# Controll.net
KiCad netlist of a schematic drawn in Altium Designer
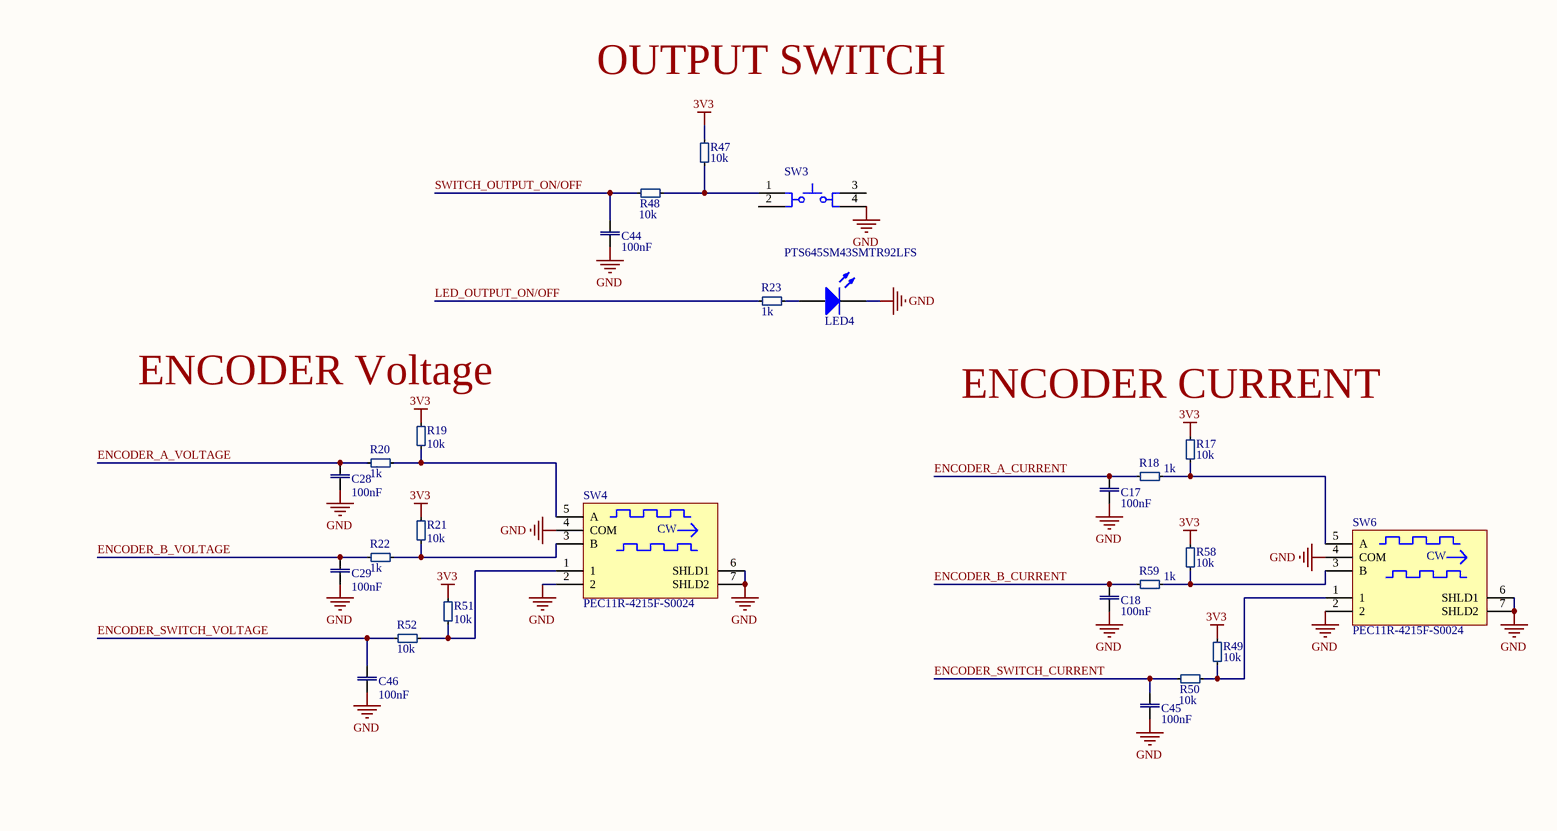
[diagram p0: Controll.SchDoc, top left]
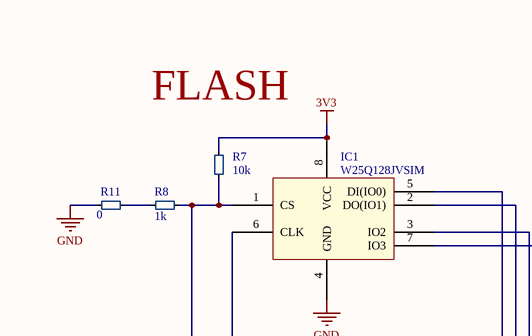
[diagram p1: Controll.SchDoc, top right]
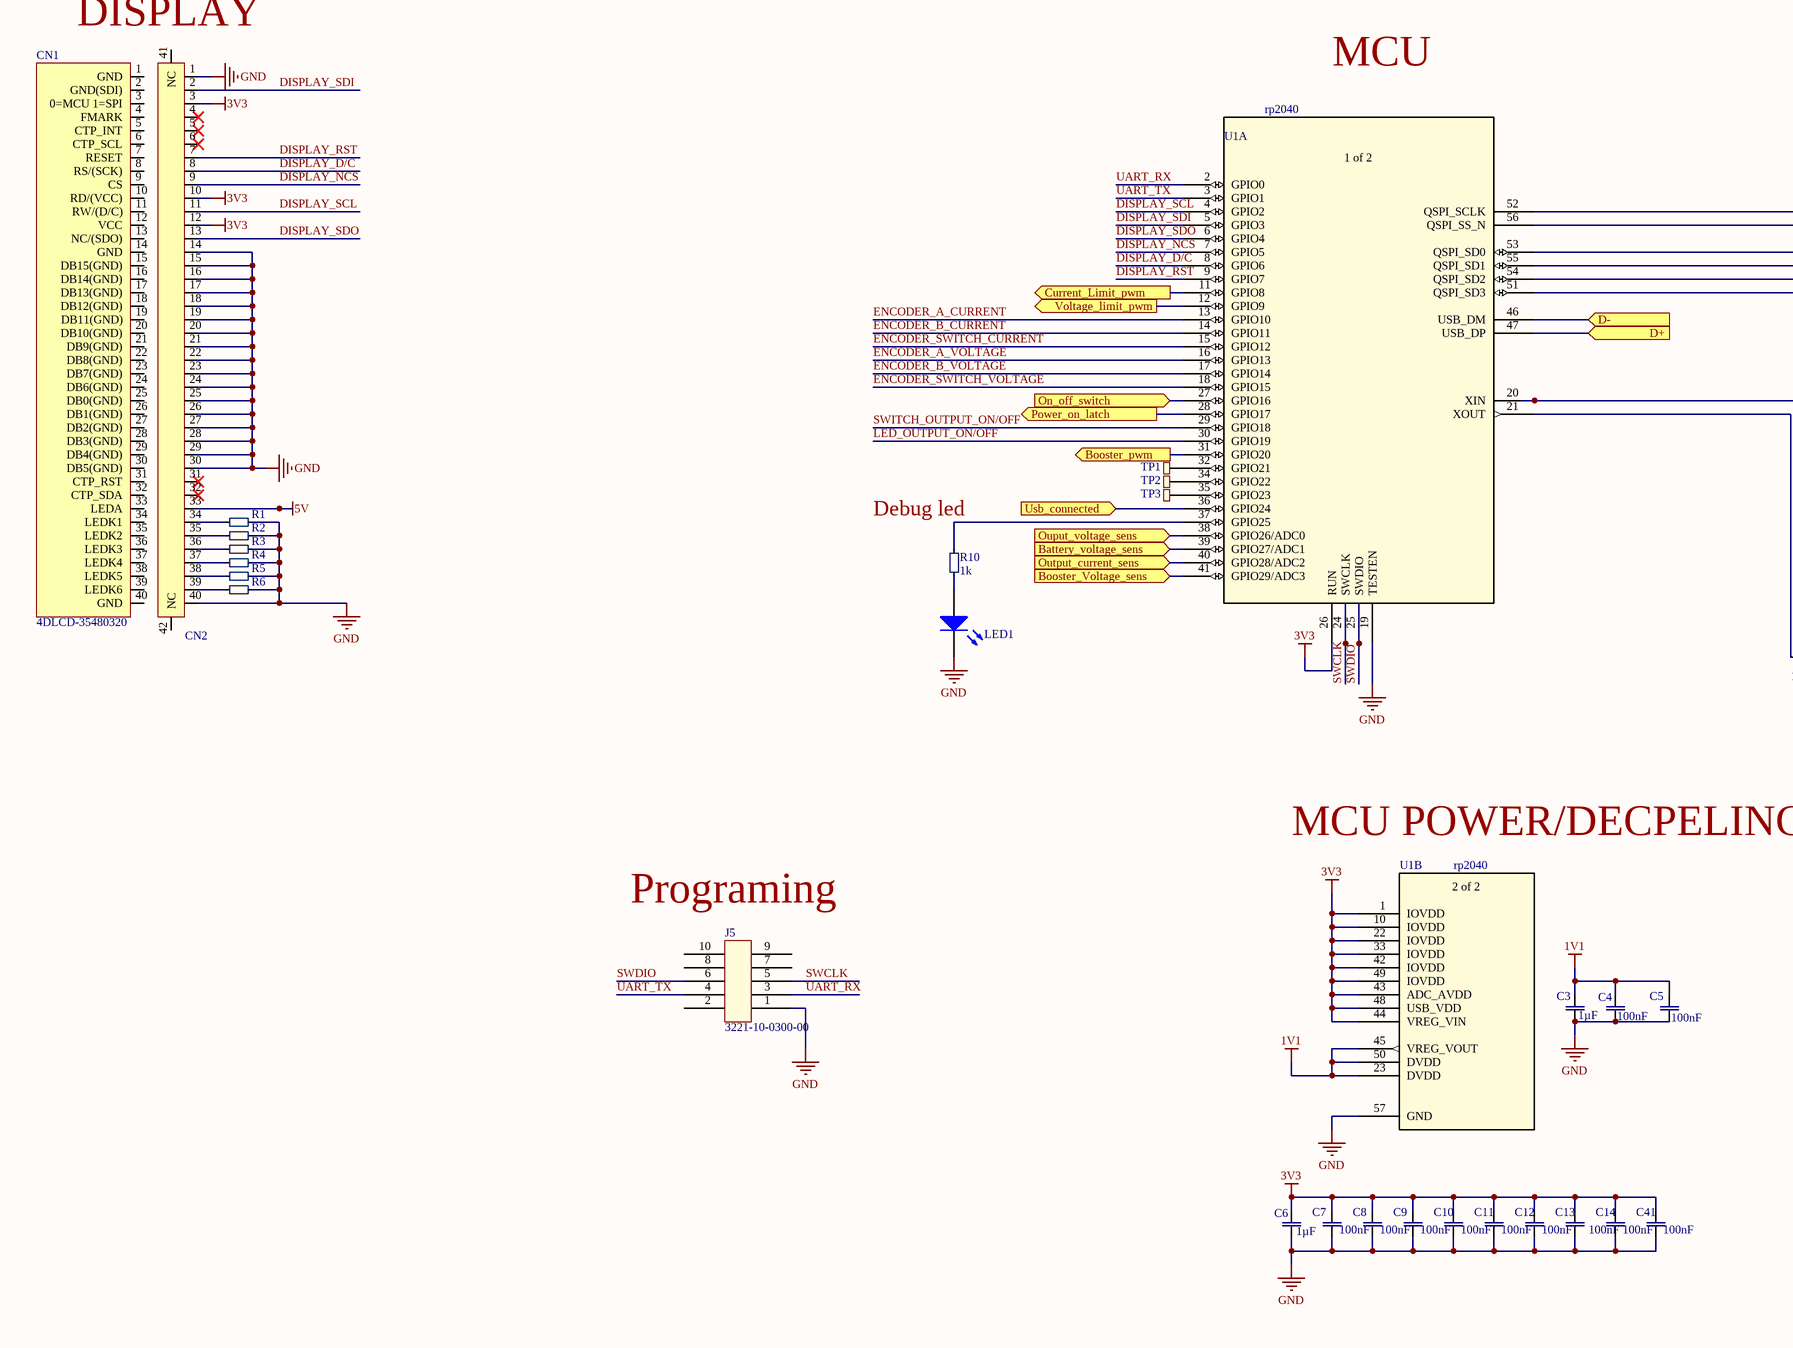
[diagram p2: Controll.SchDoc, bottom left]
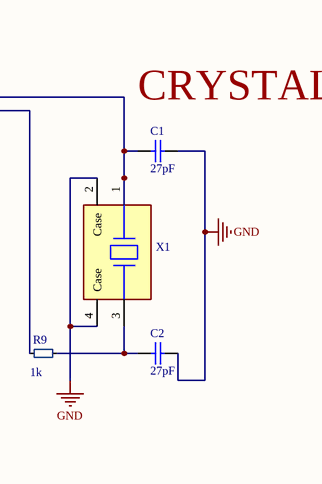
[diagram p3: Controll.SchDoc, bottom right]

(export (version "E")
  (design (tool "Eeschema 10.0.6"))
  (components
    (comp (ref "C1")
      (value "04025A270KAT2A")
      (footprint "cap0402")
      (description "0402 27 pF 50 V ±10 % Tolerance C0G/NP0 SMT Multilayer Ceramic Capacitor")
      (fields
        (field (name "CAPACITANCE") "27pF")
        (field (name "TOLERANCE") "10%")
        (field (name "LCSC PART#") "C2168514")
      )
      (libsource (lib "concord server") (part "CAP"))
    )
    (comp (ref "C2")
      (value "04025A270KAT2A")
      (footprint "cap0402")
      (description "0402 27 pF 50 V ±10 % Tolerance C0G/NP0 SMT Multilayer Ceramic Capacitor")
      (fields
        (field (name "CAPACITANCE") "27pF")
        (field (name "TOLERANCE") "10%")
        (field (name "LCSC PART#") "C2168514")
      )
      (libsource (lib "concord server") (part "CAP"))
    )
    (comp (ref "C3")
      (value "CL21B105KBFNNNG")
      (footprint "CAP0805")
      (description "SAMSUNG ELECTRO-MECHANICS - CL21B105KBFNNNG - MLCC CAPACITORS")
      (fields
        (field (name "VOLTAGE") "50V")
        (field (name "CAPACITANCE") "1µF")
        (field (name "TOLERANCE") "10%")
      )
      (libsource (lib "concord server") (part "Capasitor_keramic_generic"))
    )
    (comp (ref "C4")
      (value "GRM155R71H104ME14D")
      (footprint "cap0402")
      (description "0402 0.1 uF 50 V ±20% Tolerance X7R SMT Monolithic Ceramic Chip Capacitor")
      (fields
        (field (name "CAPACITANCE") "100nF")
        (field (name "TOLERANCE") "20%")
        (field (name "LCSC PART#") "C182412")
      )
      (libsource (lib "concord server") (part "Capasitor_keramic_generic"))
    )
    (comp (ref "C5")
      (value "GRM155R71H104ME14D")
      (footprint "cap0402")
      (description "0402 0.1 uF 50 V ±20% Tolerance X7R SMT Monolithic Ceramic Chip Capacitor")
      (fields
        (field (name "CAPACITANCE") "100nF")
        (field (name "TOLERANCE") "20%")
        (field (name "LCSC PART#") "C182412")
      )
      (libsource (lib "concord server") (part "Capasitor_keramic_generic"))
    )
    (comp (ref "C6")
      (value "CL21B105KBFNNNG")
      (footprint "CAP0805")
      (description "SAMSUNG ELECTRO-MECHANICS - CL21B105KBFNNNG - MLCC CAPACITORS")
      (fields
        (field (name "VOLTAGE") "50V")
        (field (name "CAPACITANCE") "1µF")
        (field (name "TOLERANCE") "10%")
      )
      (libsource (lib "concord server") (part "Capasitor_keramic_generic"))
    )
    (comp (ref "C7")
      (value "GRM155R71H104ME14D")
      (footprint "cap0402")
      (description "0402 0.1 uF 50 V ±20% Tolerance X7R SMT Monolithic Ceramic Chip Capacitor")
      (fields
        (field (name "CAPACITANCE") "100nF")
        (field (name "TOLERANCE") "20%")
        (field (name "LCSC PART#") "C182412")
      )
      (libsource (lib "concord server") (part "Capasitor_keramic_generic"))
    )
    (comp (ref "C8")
      (value "GRM155R71H104ME14D")
      (footprint "cap0402")
      (description "0402 0.1 uF 50 V ±20% Tolerance X7R SMT Monolithic Ceramic Chip Capacitor")
      (fields
        (field (name "CAPACITANCE") "100nF")
        (field (name "TOLERANCE") "20%")
        (field (name "LCSC PART#") "C182412")
      )
      (libsource (lib "concord server") (part "Capasitor_keramic_generic"))
    )
    (comp (ref "C9")
      (value "GRM155R71H104ME14D")
      (footprint "cap0402")
      (description "0402 0.1 uF 50 V ±20% Tolerance X7R SMT Monolithic Ceramic Chip Capacitor")
      (fields
        (field (name "CAPACITANCE") "100nF")
        (field (name "TOLERANCE") "20%")
        (field (name "LCSC PART#") "C182412")
      )
      (libsource (lib "concord server") (part "Capasitor_keramic_generic"))
    )
    (comp (ref "C10")
      (value "GRM155R71H104ME14D")
      (footprint "cap0402")
      (description "0402 0.1 uF 50 V ±20% Tolerance X7R SMT Monolithic Ceramic Chip Capacitor")
      (fields
        (field (name "CAPACITANCE") "100nF")
        (field (name "TOLERANCE") "20%")
        (field (name "LCSC PART#") "C182412")
      )
      (libsource (lib "concord server") (part "Capasitor_keramic_generic"))
    )
    (comp (ref "C11")
      (value "GRM155R71H104ME14D")
      (footprint "cap0402")
      (description "0402 0.1 uF 50 V ±20% Tolerance X7R SMT Monolithic Ceramic Chip Capacitor")
      (fields
        (field (name "CAPACITANCE") "100nF")
        (field (name "TOLERANCE") "20%")
        (field (name "LCSC PART#") "C182412")
      )
      (libsource (lib "concord server") (part "Capasitor_keramic_generic"))
    )
    (comp (ref "C12")
      (value "GRM155R71H104ME14D")
      (footprint "cap0402")
      (description "0402 0.1 uF 50 V ±20% Tolerance X7R SMT Monolithic Ceramic Chip Capacitor")
      (fields
        (field (name "CAPACITANCE") "100nF")
        (field (name "TOLERANCE") "20%")
        (field (name "LCSC PART#") "C182412")
      )
      (libsource (lib "concord server") (part "Capasitor_keramic_generic"))
    )
    (comp (ref "C13")
      (value "GRM155R71H104ME14D")
      (footprint "cap0402")
      (description "0402 0.1 uF 50 V ±20% Tolerance X7R SMT Monolithic Ceramic Chip Capacitor")
      (fields
        (field (name "CAPACITANCE") "100nF")
        (field (name "TOLERANCE") "20%")
        (field (name "LCSC PART#") "C182412")
      )
      (libsource (lib "concord server") (part "Capasitor_keramic_generic"))
    )
    (comp (ref "C14")
      (value "GRM155R71H104ME14D")
      (footprint "cap0402")
      (description "0402 0.1 uF 50 V ±20% Tolerance X7R SMT Monolithic Ceramic Chip Capacitor")
      (fields
        (field (name "CAPACITANCE") "100nF")
        (field (name "TOLERANCE") "20%")
        (field (name "LCSC PART#") "C182412")
      )
      (libsource (lib "concord server") (part "Capasitor_keramic_generic"))
    )
    (comp (ref "C17")
      (value "GRM155R71H104ME14D")
      (footprint "cap0402")
      (description "0402 0.1 uF 50 V ±20% Tolerance X7R SMT Monolithic Ceramic Chip Capacitor")
      (fields
        (field (name "CAPACITANCE") "100nF")
        (field (name "TOLERANCE") "20%")
        (field (name "LCSC PART#") "C182412")
      )
      (libsource (lib "concord server") (part "Capasitor_keramic_generic"))
    )
    (comp (ref "C18")
      (value "GRM155R71H104ME14D")
      (footprint "cap0402")
      (description "0402 0.1 uF 50 V ±20% Tolerance X7R SMT Monolithic Ceramic Chip Capacitor")
      (fields
        (field (name "CAPACITANCE") "100nF")
        (field (name "TOLERANCE") "20%")
        (field (name "LCSC PART#") "C182412")
      )
      (libsource (lib "concord server") (part "Capasitor_keramic_generic"))
    )
    (comp (ref "C28")
      (value "GRM155R71H104ME14D")
      (footprint "cap0402")
      (description "0402 0.1 uF 50 V ±20% Tolerance X7R SMT Monolithic Ceramic Chip Capacitor")
      (fields
        (field (name "CAPACITANCE") "100nF")
        (field (name "TOLERANCE") "20%")
        (field (name "LCSC PART#") "C182412")
      )
      (libsource (lib "concord server") (part "Capasitor_keramic_generic"))
    )
    (comp (ref "C29")
      (value "GRM155R71H104ME14D")
      (footprint "cap0402")
      (description "0402 0.1 uF 50 V ±20% Tolerance X7R SMT Monolithic Ceramic Chip Capacitor")
      (fields
        (field (name "CAPACITANCE") "100nF")
        (field (name "TOLERANCE") "20%")
        (field (name "LCSC PART#") "C182412")
      )
      (libsource (lib "concord server") (part "Capasitor_keramic_generic"))
    )
    (comp (ref "C41")
      (value "GRM155R71H104ME14D")
      (footprint "cap0402")
      (description "0402 0.1 uF 50 V ±20% Tolerance X7R SMT Monolithic Ceramic Chip Capacitor")
      (fields
        (field (name "CAPACITANCE") "100nF")
        (field (name "TOLERANCE") "20%")
        (field (name "LCSC PART#") "C182412")
      )
      (libsource (lib "concord server") (part "Capasitor_keramic_generic"))
    )
    (comp (ref "C44")
      (value "GRM155R71H104ME14D")
      (footprint "cap0402")
      (description "0402 0.1 uF 50 V ±20% Tolerance X7R SMT Monolithic Ceramic Chip Capacitor")
      (fields
        (field (name "CAPACITANCE") "100nF")
        (field (name "TOLERANCE") "20%")
        (field (name "LCSC PART#") "C182412")
      )
      (libsource (lib "concord server") (part "Capasitor_keramic_generic"))
    )
    (comp (ref "C45")
      (value "GRM155R71H104ME14D")
      (footprint "cap0402")
      (description "0402 0.1 uF 50 V ±20% Tolerance X7R SMT Monolithic Ceramic Chip Capacitor")
      (fields
        (field (name "CAPACITANCE") "100nF")
        (field (name "TOLERANCE") "20%")
        (field (name "LCSC PART#") "C182412")
      )
      (libsource (lib "concord server") (part "Capasitor_keramic_generic"))
    )
    (comp (ref "C46")
      (value "GRM155R71H104ME14D")
      (footprint "cap0402")
      (description "0402 0.1 uF 50 V ±20% Tolerance X7R SMT Monolithic Ceramic Chip Capacitor")
      (fields
        (field (name "CAPACITANCE") "100nF")
        (field (name "TOLERANCE") "20%")
        (field (name "LCSC PART#") "C182412")
      )
      (libsource (lib "concord server") (part "Capasitor_keramic_generic"))
    )
    (comp (ref "CN1") (value "4DLCD-35480320") (libsource (lib "concord server") (part "4DLCD-35480320")))
    (comp (ref "CN2")
      (value "505110-4091")
      (footprint "505110-4091-Footprint-1")
      (libsource (lib "concord server") (part "505110-4091"))
    )
    (comp (ref "IC1")
      (value "W25Q128JVSIM")
      (footprint "SOIC127P780X195-8N")
      (description "NOR Flash Serial (SPI, Dual SPI, Quad SPI) 3V/3.3V 128M-bit 16M x 8 6ns 8-Pin SOIC Tube")
      (fields (field (name "LCSC PART#") "C2613930"))
      (libsource (lib "concord server") (part "W25Q128JVSIM-Symbol-1"))
    )
    (comp (ref "J5")
      (value "3221-10-0300-00")
      (footprint "New footprint 1")
      (description "Conn Shrouded Header HDR 10 POS 1.27mm Solder ST SMD")
      (libsource (lib "concord server") (part "3221-10-0300-00-Symbol-1"))
    )
    (comp (ref "LED1")
      (value "150080BS75000")
      (footprint "0805_A")
      (description "SMD LED blue 3.5 V 0805, 150080BS75000, Würth Elektronik")
      (libsource (lib "concord server") (part "WE-LED_K1A2-2"))
    )
    (comp (ref "LED4")
      (value "150080BS75000")
      (footprint "0805_A")
      (description "SMD LED blue 3.5 V 0805, 150080BS75000, Würth Elektronik")
      (libsource (lib "concord server") (part "WE-LED_K1A2-2"))
    )
    (comp (ref "R1")
      (value "RC0402FR-07100RL")
      (footprint "RESC0402(1005)_N")
      (description "Res General Purpose Thick Film 0402 100 Ohm 1% 1/16W ±100ppm/°C Molded SMD Paper T/R")
      (fields (field (name "TOLERANCE") "1%") (field (name "LCSC PART#") "C106232"))
      (libsource (lib "concord server") (part "resistor_european"))
    )
    (comp (ref "R2")
      (value "RC0402FR-07100RL")
      (footprint "RESC0402(1005)_N")
      (description "Res General Purpose Thick Film 0402 100 Ohm 1% 1/16W ±100ppm/°C Molded SMD Paper T/R")
      (fields (field (name "TOLERANCE") "1%") (field (name "LCSC PART#") "C106232"))
      (libsource (lib "concord server") (part "resistor_european"))
    )
    (comp (ref "R3")
      (value "RC0402FR-07100RL")
      (footprint "RESC0402(1005)_N")
      (description "Res General Purpose Thick Film 0402 100 Ohm 1% 1/16W ±100ppm/°C Molded SMD Paper T/R")
      (fields (field (name "TOLERANCE") "1%") (field (name "LCSC PART#") "C106232"))
      (libsource (lib "concord server") (part "resistor_european"))
    )
    (comp (ref "R4")
      (value "RC0402FR-07100RL")
      (footprint "RESC0402(1005)_N")
      (description "Res General Purpose Thick Film 0402 100 Ohm 1% 1/16W ±100ppm/°C Molded SMD Paper T/R")
      (fields (field (name "TOLERANCE") "1%") (field (name "LCSC PART#") "C106232"))
      (libsource (lib "concord server") (part "resistor_european"))
    )
    (comp (ref "R5")
      (value "RC0402FR-07100RL")
      (footprint "RESC0402(1005)_N")
      (description "Res General Purpose Thick Film 0402 100 Ohm 1% 1/16W ±100ppm/°C Molded SMD Paper T/R")
      (fields (field (name "TOLERANCE") "1%") (field (name "LCSC PART#") "C106232"))
      (libsource (lib "concord server") (part "resistor_european"))
    )
    (comp (ref "R6")
      (value "RC0402FR-07100RL")
      (footprint "RESC0402(1005)_N")
      (description "Res General Purpose Thick Film 0402 100 Ohm 1% 1/16W ±100ppm/°C Molded SMD Paper T/R")
      (fields (field (name "TOLERANCE") "1%") (field (name "LCSC PART#") "C106232"))
      (libsource (lib "concord server") (part "resistor_european"))
    )
    (comp (ref "R7")
      (value "RC0402FR-0710KL")
      (footprint "SMD_0402(1005)_M")
      (description "Surface Mount Thick Film Resistor, Rc Series, 10 Kohm, 62.5 Mw, - 1%, 50 V, 0402 [1005 Metric]")
      (fields
        (field (name "RESISTANCE") "10k")
        (field (name "TOLERANCE") "1%")
        (field (name "LCSC PART#") "C60490")
      )
      (libsource (lib "concord server") (part "resistor_european"))
    )
    (comp (ref "R8")
      (value "RC0402FR-071KL")
      (footprint "SMD_0402(1005)_M")
      (description "Surface Mount Chip Resistor, Thick Film, RC Series, 1 kohm, 62.5 mW, 1%, 50 V, 0402 [1005 Metric]")
      (fields
        (field (name "RESISTANCE") "1k")
        (field (name "TOLERANCE") "1%")
        (field (name "LCSC PART#") "C2935237")
      )
      (libsource (lib "concord server") (part "resistor_european"))
    )
    (comp (ref "R9")
      (value "RC0402FR-071KL")
      (footprint "SMD_0402(1005)_M")
      (description "Surface Mount Chip Resistor, Thick Film, RC Series, 1 kohm, 62.5 mW, 1%, 50 V, 0402 [1005 Metric]")
      (fields
        (field (name "RESISTANCE") "1k")
        (field (name "TOLERANCE") "1%")
        (field (name "LCSC PART#") "C2935237")
      )
      (libsource (lib "concord server") (part "resistor_european"))
    )
    (comp (ref "R10")
      (value "RC0402FR-071KL")
      (footprint "SMD_0402(1005)_M")
      (description "Surface Mount Chip Resistor, Thick Film, RC Series, 1 kohm, 62.5 mW, 1%, 50 V, 0402 [1005 Metric]")
      (fields
        (field (name "RESISTANCE") "1k")
        (field (name "TOLERANCE") "1%")
        (field (name "LCSC PART#") "C2935237")
      )
      (libsource (lib "concord server") (part "resistor_european"))
    )
    (comp (ref "R11")
      (value "RC0402FR-070RL")
      (footprint "SMD_0402(1005)_M")
      (description "Res Thick Film 0402 0 Ohm Molded SMD SMD Paper T/R")
      (fields
        (field (name "RESISTANCE") "0")
        (field (name "TOLERANCE") "1%")
        (field (name "LCSC PART#") "C106231")
      )
      (libsource (lib "concord server") (part "resistor_european"))
    )
    (comp (ref "R17")
      (value "RC0402FR-0710KL")
      (footprint "SMD_0402(1005)_M")
      (description "Surface Mount Thick Film Resistor, Rc Series, 10 Kohm, 62.5 Mw, - 1%, 50 V, 0402 [1005 Metric]")
      (fields
        (field (name "RESISTANCE") "10k")
        (field (name "TOLERANCE") "1%")
        (field (name "LCSC PART#") "C60490")
      )
      (libsource (lib "concord server") (part "resistor_european"))
    )
    (comp (ref "R18")
      (value "RC0402FR-071KL")
      (footprint "SMD_0402(1005)_M")
      (description "Surface Mount Chip Resistor, Thick Film, RC Series, 1 kohm, 62.5 mW, 1%, 50 V, 0402 [1005 Metric]")
      (fields
        (field (name "RESISTANCE") "1k")
        (field (name "TOLERANCE") "1%")
        (field (name "LCSC PART#") "C2935237")
      )
      (libsource (lib "concord server") (part "resistor_european"))
    )
    (comp (ref "R19")
      (value "RC0402FR-0710KL")
      (footprint "SMD_0402(1005)_M")
      (description "Surface Mount Thick Film Resistor, Rc Series, 10 Kohm, 62.5 Mw, - 1%, 50 V, 0402 [1005 Metric]")
      (fields
        (field (name "RESISTANCE") "10k")
        (field (name "TOLERANCE") "1%")
        (field (name "LCSC PART#") "C60490")
      )
      (libsource (lib "concord server") (part "resistor_european"))
    )
    (comp (ref "R20")
      (value "RC0402FR-071KL")
      (footprint "SMD_0402(1005)_M")
      (description "Surface Mount Chip Resistor, Thick Film, RC Series, 1 kohm, 62.5 mW, 1%, 50 V, 0402 [1005 Metric]")
      (fields
        (field (name "RESISTANCE") "1k")
        (field (name "TOLERANCE") "1%")
        (field (name "LCSC PART#") "C2935237")
      )
      (libsource (lib "concord server") (part "resistor_european"))
    )
    (comp (ref "R21")
      (value "RC0402FR-0710KL")
      (footprint "SMD_0402(1005)_M")
      (description "Surface Mount Thick Film Resistor, Rc Series, 10 Kohm, 62.5 Mw, - 1%, 50 V, 0402 [1005 Metric]")
      (fields
        (field (name "RESISTANCE") "10k")
        (field (name "TOLERANCE") "1%")
        (field (name "LCSC PART#") "C60490")
      )
      (libsource (lib "concord server") (part "resistor_european"))
    )
    (comp (ref "R22")
      (value "RC0402FR-071KL")
      (footprint "SMD_0402(1005)_M")
      (description "Surface Mount Chip Resistor, Thick Film, RC Series, 1 kohm, 62.5 mW, 1%, 50 V, 0402 [1005 Metric]")
      (fields
        (field (name "RESISTANCE") "1k")
        (field (name "TOLERANCE") "1%")
        (field (name "LCSC PART#") "C2935237")
      )
      (libsource (lib "concord server") (part "resistor_european"))
    )
    (comp (ref "R23")
      (value "RC0402FR-071KL")
      (footprint "SMD_0402(1005)_M")
      (description "Surface Mount Chip Resistor, Thick Film, RC Series, 1 kohm, 62.5 mW, 1%, 50 V, 0402 [1005 Metric]")
      (fields
        (field (name "RESISTANCE") "1k")
        (field (name "TOLERANCE") "1%")
        (field (name "LCSC PART#") "C2935237")
      )
      (libsource (lib "concord server") (part "resistor_european"))
    )
    (comp (ref "R47")
      (value "RC0402FR-0710KL")
      (footprint "SMD_0402(1005)_M")
      (description "Surface Mount Thick Film Resistor, Rc Series, 10 Kohm, 62.5 Mw, - 1%, 50 V, 0402 [1005 Metric]")
      (fields
        (field (name "RESISTANCE") "10k")
        (field (name "TOLERANCE") "1%")
        (field (name "LCSC PART#") "C60490")
      )
      (libsource (lib "concord server") (part "resistor_european"))
    )
    (comp (ref "R48")
      (value "RC0402FR-0710KL")
      (footprint "SMD_0402(1005)_M")
      (description "Surface Mount Thick Film Resistor, Rc Series, 10 Kohm, 62.5 Mw, - 1%, 50 V, 0402 [1005 Metric]")
      (fields
        (field (name "RESISTANCE") "10k")
        (field (name "TOLERANCE") "1%")
        (field (name "LCSC PART#") "C60490")
      )
      (libsource (lib "concord server") (part "resistor_european"))
    )
    (comp (ref "R49")
      (value "RC0402FR-0710KL")
      (footprint "SMD_0402(1005)_M")
      (description "Surface Mount Thick Film Resistor, Rc Series, 10 Kohm, 62.5 Mw, - 1%, 50 V, 0402 [1005 Metric]")
      (fields
        (field (name "RESISTANCE") "10k")
        (field (name "TOLERANCE") "1%")
        (field (name "LCSC PART#") "C60490")
      )
      (libsource (lib "concord server") (part "resistor_european"))
    )
    (comp (ref "R50")
      (value "RC0402FR-0710KL")
      (footprint "SMD_0402(1005)_M")
      (description "Surface Mount Thick Film Resistor, Rc Series, 10 Kohm, 62.5 Mw, - 1%, 50 V, 0402 [1005 Metric]")
      (fields
        (field (name "RESISTANCE") "10k")
        (field (name "TOLERANCE") "1%")
        (field (name "LCSC PART#") "C60490")
      )
      (libsource (lib "concord server") (part "resistor_european"))
    )
    (comp (ref "R51")
      (value "RC0402FR-0710KL")
      (footprint "SMD_0402(1005)_M")
      (description "Surface Mount Thick Film Resistor, Rc Series, 10 Kohm, 62.5 Mw, - 1%, 50 V, 0402 [1005 Metric]")
      (fields
        (field (name "RESISTANCE") "10k")
        (field (name "TOLERANCE") "1%")
        (field (name "LCSC PART#") "C60490")
      )
      (libsource (lib "concord server") (part "resistor_european"))
    )
    (comp (ref "R52")
      (value "RC0402FR-0710KL")
      (footprint "SMD_0402(1005)_M")
      (description "Surface Mount Thick Film Resistor, Rc Series, 10 Kohm, 62.5 Mw, - 1%, 50 V, 0402 [1005 Metric]")
      (fields
        (field (name "RESISTANCE") "10k")
        (field (name "TOLERANCE") "1%")
        (field (name "LCSC PART#") "C60490")
      )
      (libsource (lib "concord server") (part "resistor_european"))
    )
    (comp (ref "R58")
      (value "RC0402FR-0710KL")
      (footprint "SMD_0402(1005)_M")
      (description "Surface Mount Thick Film Resistor, Rc Series, 10 Kohm, 62.5 Mw, - 1%, 50 V, 0402 [1005 Metric]")
      (fields
        (field (name "RESISTANCE") "10k")
        (field (name "TOLERANCE") "1%")
        (field (name "LCSC PART#") "C60490")
      )
      (libsource (lib "concord server") (part "resistor_european"))
    )
    (comp (ref "R59")
      (value "RC0402FR-071KL")
      (footprint "SMD_0402(1005)_M")
      (description "Surface Mount Chip Resistor, Thick Film, RC Series, 1 kohm, 62.5 mW, 1%, 50 V, 0402 [1005 Metric]")
      (fields
        (field (name "RESISTANCE") "1k")
        (field (name "TOLERANCE") "1%")
        (field (name "LCSC PART#") "C2935237")
      )
      (libsource (lib "concord server") (part "resistor_european"))
    )
    (comp (ref "SW3")
      (value "PTS645SM43SMTR92LFS")
      (footprint "CKCP-PTS645S_V")
      (fields (field (name "LCSC PART#") "C221880"))
      (libsource (lib "concord server") (part "SW-SPST-NO-4"))
    )
    (comp (ref "SW4")
      (value "PEC11R-4215F-S0024")
      (footprint "BOUR-PEC11R-4XXXF-SXXXX_V")
      (fields (field (name "LCSC PART#") "C143790"))
      (libsource (lib "concord server") (part "SW-ENCODER-5"))
    )
    (comp (ref "SW6")
      (value "PEC11R-4215F-S0024")
      (footprint "BOUR-PEC11R-4XXXF-SXXXX_V")
      (fields (field (name "LCSC PART#") "C143790"))
      (libsource (lib "concord server") (part "SW-ENCODER-5"))
    )
    (comp (ref "TP1")
      (value "testpoit")
      (footprint "testpoit-Footprint-1")
      (description "2 mm singel sided testpoint")
      (libsource (lib "concord server") (part "testpoint"))
    )
    (comp (ref "TP2")
      (value "testpoit")
      (footprint "testpoit-Footprint-1")
      (description "2 mm singel sided testpoint")
      (libsource (lib "concord server") (part "testpoint"))
    )
    (comp (ref "TP3")
      (value "testpoit")
      (footprint "testpoit-Footprint-1")
      (description "2 mm singel sided testpoint")
      (libsource (lib "concord server") (part "testpoint"))
    )
    (comp (ref "U1")
      (value "rp2040")
      (footprint "rp2040-Footprint-1")
      (fields (field (name "LCSC PART#") "C2040"))
      (libsource (lib "concord server") (part "rp2040-Symbol-1"))
    )
    (comp (ref "X1")
      (value "FL1200112")
      (footprint "FP-FL1200112-MFG")
      (description "Crystal 12MHz ±30ppm (Tol) ±30ppm (Stability) 18pF FUND 80Ohm 4-Pin SMD T/R")
      (fields (field (name "LCSC PART#") "C1985665"))
      (libsource (lib "concord server") (part "5207c8a21b287eb3b87797a81180633"))
    )
  )
  (nets
    (net (code "1") (name "/Battery_voltage_sens") (class "Default")
      (node (ref "U1") (pin "39") (pinfunction "GPIO27/ADC1_39") (pintype "bidirectional"))
    )
    (net (code "2") (name "/Booster_Voltage_sens") (class "Default")
      (node (ref "U1") (pin "41") (pinfunction "GPIO29/ADC3_41") (pintype "bidirectional"))
    )
    (net (code "3") (name "/Booster_pwm") (class "Default")
      (node (ref "U1") (pin "31") (pinfunction "GPIO20_31") (pintype "bidirectional"))
    )
    (net (code "4") (name "/Current_Limit_pwm") (class "Default")
      (node (ref "U1") (pin "11") (pinfunction "GPIO8_11") (pintype "bidirectional"))
    )
    (net (code "5") (name "/D+") (class "Default")
      (node (ref "U1") (pin "47") (pinfunction "USB_DP_47") (pintype "passive"))
    )
    (net (code "6") (name "/D-") (class "Default")
      (node (ref "U1") (pin "46") (pinfunction "USB_DM_46") (pintype "passive"))
    )
    (net (code "7") (name "/DISPLAY_D{slash}C") (class "Default")
      (node (ref "CN2") (pin "8") (pintype "bidirectional"))
      (node (ref "U1") (pin "8") (pinfunction "GPIO6_8") (pintype "bidirectional"))
    )
    (net (code "8") (name "/DISPLAY_NCS") (class "Default")
      (node (ref "CN2") (pin "9") (pintype "bidirectional"))
      (node (ref "U1") (pin "7") (pinfunction "GPIO5_7") (pintype "bidirectional"))
    )
    (net (code "9") (name "/DISPLAY_RST") (class "Default")
      (node (ref "CN2") (pin "7") (pintype "bidirectional"))
      (node (ref "U1") (pin "9") (pinfunction "GPIO7_9") (pintype "bidirectional"))
    )
    (net (code "10") (name "/DISPLAY_SCL") (class "Default")
      (node (ref "CN2") (pin "11") (pintype "bidirectional"))
      (node (ref "U1") (pin "4") (pinfunction "GPIO2_4") (pintype "bidirectional"))
    )
    (net (code "11") (name "/DISPLAY_SDI") (class "Default")
      (node (ref "CN2") (pin "2") (pintype "bidirectional"))
      (node (ref "U1") (pin "5") (pinfunction "GPIO3_5") (pintype "bidirectional"))
    )
    (net (code "12") (name "/DISPLAY_SDO") (class "Default")
      (node (ref "CN2") (pin "13") (pintype "bidirectional"))
      (node (ref "U1") (pin "6") (pinfunction "GPIO4_6") (pintype "bidirectional"))
    )
    (net (code "13") (name "/ENCODER_A_CURRENT") (class "Default")
      (node (ref "C17") (pin "2") (pinfunction "2_2") (pintype "passive"))
      (node (ref "R18") (pin "1") (pinfunction "1_1") (pintype "passive"))
      (node (ref "U1") (pin "13") (pinfunction "GPIO10_13") (pintype "bidirectional"))
    )
    (net (code "14") (name "/ENCODER_A_VOLTAGE") (class "Default")
      (node (ref "C28") (pin "2") (pinfunction "2_2") (pintype "passive"))
      (node (ref "R20") (pin "1") (pinfunction "1_1") (pintype "passive"))
      (node (ref "U1") (pin "16") (pinfunction "GPIO13_16") (pintype "bidirectional"))
    )
    (net (code "15") (name "/ENCODER_B_CURRENT") (class "Default")
      (node (ref "C18") (pin "2") (pinfunction "2_2") (pintype "passive"))
      (node (ref "R59") (pin "1") (pinfunction "1_1") (pintype "passive"))
      (node (ref "U1") (pin "14") (pinfunction "GPIO11_14") (pintype "bidirectional"))
    )
    (net (code "16") (name "/ENCODER_B_VOLTAGE") (class "Default")
      (node (ref "C29") (pin "2") (pinfunction "2_2") (pintype "passive"))
      (node (ref "R22") (pin "1") (pinfunction "1_1") (pintype "passive"))
      (node (ref "U1") (pin "17") (pinfunction "GPIO14_17") (pintype "bidirectional"))
    )
    (net (code "17") (name "/ENCODER_SWITCH_CURRENT") (class "Default")
      (node (ref "C45") (pin "2") (pinfunction "2_2") (pintype "passive"))
      (node (ref "R50") (pin "2") (pinfunction "2_2") (pintype "passive"))
      (node (ref "U1") (pin "15") (pinfunction "GPIO12_15") (pintype "bidirectional"))
    )
    (net (code "18") (name "/ENCODER_SWITCH_VOLTAGE") (class "Default")
      (node (ref "C46") (pin "2") (pinfunction "2_2") (pintype "passive"))
      (node (ref "R52") (pin "2") (pinfunction "2_2") (pintype "passive"))
      (node (ref "U1") (pin "18") (pinfunction "GPIO15_18") (pintype "bidirectional"))
    )
    (net (code "19") (name "/LED_OUTPUT_ON{slash}OFF") (class "Default")
      (node (ref "R23") (pin "2") (pinfunction "2_2") (pintype "passive"))
      (node (ref "U1") (pin "30") (pinfunction "GPIO19_30") (pintype "bidirectional"))
    )
    (net (code "20") (name "/On_off_switch") (class "Default")
      (node (ref "U1") (pin "27") (pinfunction "GPIO16_27") (pintype "bidirectional"))
    )
    (net (code "21") (name "/Ouput_voltage_sens") (class "Default")
      (node (ref "U1") (pin "38") (pinfunction "GPIO26/ADC0_38") (pintype "bidirectional"))
    )
    (net (code "22") (name "/Output_current_sens") (class "Default")
      (node (ref "U1") (pin "40") (pinfunction "GPIO28/ADC2_40") (pintype "bidirectional"))
    )
    (net (code "23") (name "/Power_on_latch") (class "Default")
      (node (ref "U1") (pin "28") (pinfunction "GPIO17_28") (pintype "bidirectional"))
    )
    (net (code "24") (name "/SWCLK") (class "Default")
      (node (ref "J5") (pin "5") (pinfunction "5_5") (pintype "passive"))
      (node (ref "U1") (pin "24") (pinfunction "SWCLK_24") (pintype "passive"))
    )
    (net (code "25") (name "/SWDIO") (class "Default")
      (node (ref "J5") (pin "6") (pinfunction "6_6") (pintype "passive"))
      (node (ref "U1") (pin "25") (pinfunction "SWDIO_25") (pintype "passive"))
    )
    (net (code "26") (name "/SWITCH_OUTPUT_ON{slash}OFF") (class "Default")
      (node (ref "C44") (pin "2") (pinfunction "2_2") (pintype "passive"))
      (node (ref "R48") (pin "2") (pinfunction "2_2") (pintype "passive"))
      (node (ref "U1") (pin "29") (pinfunction "GPIO18_29") (pintype "bidirectional"))
    )
    (net (code "27") (name "/UART_RX") (class "Default")
      (node (ref "J5") (pin "3") (pinfunction "3_3") (pintype "passive"))
      (node (ref "U1") (pin "2") (pinfunction "GPIO0_2") (pintype "bidirectional"))
    )
    (net (code "28") (name "/UART_TX") (class "Default")
      (node (ref "J5") (pin "4") (pinfunction "4_4") (pintype "passive"))
      (node (ref "U1") (pin "3") (pinfunction "GPIO1_3") (pintype "bidirectional"))
    )
    (net (code "29") (name "/Usb_connected") (class "Default")
      (node (ref "U1") (pin "36") (pinfunction "GPIO24_36") (pintype "bidirectional"))
    )
    (net (code "30") (name "/Voltage_limit_pwm") (class "Default")
      (node (ref "U1") (pin "12") (pinfunction "GPIO9_12") (pintype "bidirectional"))
    )
    (net (code "31") (name "1V1") (class "Default")
      (node (ref "C3") (pin "2") (pinfunction "2_2") (pintype "passive"))
      (node (ref "C4") (pin "2") (pinfunction "2_2") (pintype "passive"))
      (node (ref "C5") (pin "2") (pinfunction "2_2") (pintype "passive"))
      (node (ref "U1") (pin "23") (pinfunction "DVDD_23") (pintype "power_in"))
      (node (ref "U1") (pin "45") (pinfunction "VREG_VOUT_45") (pintype "output"))
      (node (ref "U1") (pin "50") (pinfunction "DVDD_50") (pintype "power_in"))
    )
    (net (code "32") (name "3V3") (class "Default")
      (node (ref "C10") (pin "2") (pinfunction "2_2") (pintype "passive"))
      (node (ref "C11") (pin "2") (pinfunction "2_2") (pintype "passive"))
      (node (ref "C12") (pin "2") (pinfunction "2_2") (pintype "passive"))
      (node (ref "C13") (pin "2") (pinfunction "2_2") (pintype "passive"))
      (node (ref "C14") (pin "2") (pinfunction "2_2") (pintype "passive"))
      (node (ref "C41") (pin "2") (pinfunction "2_2") (pintype "passive"))
      (node (ref "C6") (pin "2") (pinfunction "2_2") (pintype "passive"))
      (node (ref "C7") (pin "2") (pinfunction "2_2") (pintype "passive"))
      (node (ref "C8") (pin "2") (pinfunction "2_2") (pintype "passive"))
      (node (ref "C9") (pin "2") (pinfunction "2_2") (pintype "passive"))
      (node (ref "CN2") (pin "10") (pintype "bidirectional"))
      (node (ref "CN2") (pin "12") (pintype "bidirectional"))
      (node (ref "CN2") (pin "3") (pintype "bidirectional"))
      (node (ref "IC1") (pin "8") (pinfunction "VCC_8") (pintype "passive"))
      (node (ref "R17") (pin "2") (pinfunction "2_2") (pintype "passive"))
      (node (ref "R19") (pin "2") (pinfunction "2_2") (pintype "passive"))
      (node (ref "R21") (pin "2") (pinfunction "2_2") (pintype "passive"))
      (node (ref "R47") (pin "2") (pinfunction "2_2") (pintype "passive"))
      (node (ref "R49") (pin "2") (pinfunction "2_2") (pintype "passive"))
      (node (ref "R51") (pin "2") (pinfunction "2_2") (pintype "passive"))
      (node (ref "R58") (pin "2") (pinfunction "2_2") (pintype "passive"))
      (node (ref "R7") (pin "2") (pinfunction "2_2") (pintype "passive"))
      (node (ref "U1") (pin "1") (pinfunction "IOVDD_1") (pintype "power_in"))
      (node (ref "U1") (pin "10") (pinfunction "IOVDD_10") (pintype "power_in"))
      (node (ref "U1") (pin "22") (pinfunction "IOVDD_22") (pintype "power_in"))
      (node (ref "U1") (pin "26") (pinfunction "RUN_26") (pintype "passive"))
      (node (ref "U1") (pin "33") (pinfunction "IOVDD_33") (pintype "power_in"))
      (node (ref "U1") (pin "42") (pinfunction "IOVDD_42") (pintype "power_in"))
      (node (ref "U1") (pin "43") (pinfunction "ADC_AVDD_43") (pintype "power_in"))
      (node (ref "U1") (pin "44") (pinfunction "VREG_VIN_44") (pintype "passive"))
      (node (ref "U1") (pin "48") (pinfunction "USB_VDD_48") (pintype "power_in"))
      (node (ref "U1") (pin "49") (pinfunction "IOVDD_49") (pintype "power_in"))
    )
    (net (code "33") (name "5V") (class "Default") (node (ref "CN2") (pin "33") (pintype "bidirectional")))
    (net (code "34") (name "GND") (class "Default")
      (node (ref "C1") (pin "1") (pinfunction "1_1") (pintype "passive"))
      (node (ref "C10") (pin "1") (pinfunction "1_1") (pintype "passive"))
      (node (ref "C11") (pin "1") (pinfunction "1_1") (pintype "passive"))
      (node (ref "C12") (pin "1") (pinfunction "1_1") (pintype "passive"))
      (node (ref "C13") (pin "1") (pinfunction "1_1") (pintype "passive"))
      (node (ref "C14") (pin "1") (pinfunction "1_1") (pintype "passive"))
      (node (ref "C17") (pin "1") (pinfunction "1_1") (pintype "passive"))
      (node (ref "C18") (pin "1") (pinfunction "1_1") (pintype "passive"))
      (node (ref "C2") (pin "1") (pinfunction "1_1") (pintype "passive"))
      (node (ref "C28") (pin "1") (pinfunction "1_1") (pintype "passive"))
      (node (ref "C29") (pin "1") (pinfunction "1_1") (pintype "passive"))
      (node (ref "C3") (pin "1") (pinfunction "1_1") (pintype "passive"))
      (node (ref "C4") (pin "1") (pinfunction "1_1") (pintype "passive"))
      (node (ref "C41") (pin "1") (pinfunction "1_1") (pintype "passive"))
      (node (ref "C44") (pin "1") (pinfunction "1_1") (pintype "passive"))
      (node (ref "C45") (pin "1") (pinfunction "1_1") (pintype "passive"))
      (node (ref "C46") (pin "1") (pinfunction "1_1") (pintype "passive"))
      (node (ref "C5") (pin "1") (pinfunction "1_1") (pintype "passive"))
      (node (ref "C6") (pin "1") (pinfunction "1_1") (pintype "passive"))
      (node (ref "C7") (pin "1") (pinfunction "1_1") (pintype "passive"))
      (node (ref "C8") (pin "1") (pinfunction "1_1") (pintype "passive"))
      (node (ref "C9") (pin "1") (pinfunction "1_1") (pintype "passive"))
      (node (ref "CN2") (pin "1") (pintype "bidirectional"))
      (node (ref "CN2") (pin "14") (pintype "bidirectional"))
      (node (ref "CN2") (pin "15") (pintype "bidirectional"))
      (node (ref "CN2") (pin "16") (pintype "bidirectional"))
      (node (ref "CN2") (pin "17") (pintype "bidirectional"))
      (node (ref "CN2") (pin "18") (pintype "bidirectional"))
      (node (ref "CN2") (pin "19") (pintype "bidirectional"))
      (node (ref "CN2") (pin "20") (pintype "bidirectional"))
      (node (ref "CN2") (pin "21") (pintype "bidirectional"))
      (node (ref "CN2") (pin "22") (pintype "bidirectional"))
      (node (ref "CN2") (pin "23") (pintype "bidirectional"))
      (node (ref "CN2") (pin "24") (pintype "bidirectional"))
      (node (ref "CN2") (pin "25") (pintype "bidirectional"))
      (node (ref "CN2") (pin "26") (pintype "bidirectional"))
      (node (ref "CN2") (pin "27") (pintype "bidirectional"))
      (node (ref "CN2") (pin "28") (pintype "bidirectional"))
      (node (ref "CN2") (pin "29") (pintype "bidirectional"))
      (node (ref "CN2") (pin "30") (pintype "bidirectional"))
      (node (ref "CN2") (pin "40") (pintype "bidirectional"))
      (node (ref "IC1") (pin "4") (pinfunction "GND_4") (pintype "passive"))
      (node (ref "J5") (pin "1") (pinfunction "1_1") (pintype "passive"))
      (node (ref "LED1") (pin "1") (pinfunction "K_1") (pintype "passive"))
      (node (ref "LED4") (pin "1") (pinfunction "K_1") (pintype "passive"))
      (node (ref "R1") (pin "2") (pinfunction "2_2") (pintype "passive"))
      (node (ref "R11") (pin "1") (pinfunction "1_1") (pintype "passive"))
      (node (ref "R2") (pin "2") (pinfunction "2_2") (pintype "passive"))
      (node (ref "R3") (pin "2") (pinfunction "2_2") (pintype "passive"))
      (node (ref "R4") (pin "2") (pinfunction "2_2") (pintype "passive"))
      (node (ref "R5") (pin "2") (pinfunction "2_2") (pintype "passive"))
      (node (ref "R6") (pin "2") (pinfunction "2_2") (pintype "passive"))
      (node (ref "SW3") (pin "4") (pinfunction "4_4") (pintype "passive"))
      (node (ref "SW4") (pin "2") (pinfunction "2_2") (pintype "passive"))
      (node (ref "SW4") (pin "4") (pinfunction "COM_4") (pintype "passive"))
      (node (ref "SW4") (pin "6") (pinfunction "SHLD1_6") (pintype "passive"))
      (node (ref "SW4") (pin "7") (pinfunction "SHLD2_7") (pintype "passive"))
      (node (ref "SW6") (pin "2") (pinfunction "2_2") (pintype "passive"))
      (node (ref "SW6") (pin "4") (pinfunction "COM_4") (pintype "passive"))
      (node (ref "SW6") (pin "6") (pinfunction "SHLD1_6") (pintype "passive"))
      (node (ref "SW6") (pin "7") (pinfunction "SHLD2_7") (pintype "passive"))
      (node (ref "U1") (pin "19") (pinfunction "TESTEN_19") (pintype "passive"))
      (node (ref "U1") (pin "57") (pinfunction "GND_57") (pintype "passive"))
      (node (ref "X1") (pin "2") (pinfunction "Case_2") (pintype "passive"))
      (node (ref "X1") (pin "4") (pinfunction "Case_4") (pintype "passive"))
    )
    (net (code "35") (name "Net-(CN2-Pad34)") (class "Default")
      (node (ref "CN2") (pin "34") (pintype "bidirectional"))
      (node (ref "R1") (pin "1") (pinfunction "1_1") (pintype "passive"))
    )
    (net (code "36") (name "Net-(CN2-Pad35)") (class "Default")
      (node (ref "CN2") (pin "35") (pintype "bidirectional"))
      (node (ref "R2") (pin "1") (pinfunction "1_1") (pintype "passive"))
    )
    (net (code "37") (name "Net-(CN2-Pad36)") (class "Default")
      (node (ref "CN2") (pin "36") (pintype "bidirectional"))
      (node (ref "R3") (pin "1") (pinfunction "1_1") (pintype "passive"))
    )
    (net (code "38") (name "Net-(CN2-Pad37)") (class "Default")
      (node (ref "CN2") (pin "37") (pintype "bidirectional"))
      (node (ref "R4") (pin "1") (pinfunction "1_1") (pintype "passive"))
    )
    (net (code "39") (name "Net-(CN2-Pad38)") (class "Default")
      (node (ref "CN2") (pin "38") (pintype "bidirectional"))
      (node (ref "R5") (pin "1") (pinfunction "1_1") (pintype "passive"))
    )
    (net (code "40") (name "Net-(CN2-Pad39)") (class "Default")
      (node (ref "CN2") (pin "39") (pintype "bidirectional"))
      (node (ref "R6") (pin "1") (pinfunction "1_1") (pintype "passive"))
    )
    (net (code "41") (name "Net-(IC1-CLK)") (class "Default")
      (node (ref "IC1") (pin "6") (pinfunction "CLK_6") (pintype "passive"))
      (node (ref "U1") (pin "52") (pinfunction "QSPI_SCLK_52") (pintype "passive"))
    )
    (net (code "42") (name "Net-(IC1-CS)") (class "Default")
      (node (ref "IC1") (pin "1") (pinfunction "CS_1") (pintype "passive"))
      (node (ref "R7") (pin "1") (pinfunction "1_1") (pintype "passive"))
      (node (ref "R8") (pin "1") (pinfunction "1_1") (pintype "passive"))
      (node (ref "U1") (pin "56") (pinfunction "QSPI_SS_N_56") (pintype "passive"))
    )
    (net (code "43") (name "Net-(IC1-DI(IO0))") (class "Default")
      (node (ref "IC1") (pin "5") (pinfunction "DI(IO0)_5") (pintype "passive"))
      (node (ref "U1") (pin "53") (pinfunction "QSPI_SD0_53") (pintype "bidirectional"))
    )
    (net (code "44") (name "Net-(IC1-DO(IO1))") (class "Default")
      (node (ref "IC1") (pin "2") (pinfunction "DO(IO1)_2") (pintype "passive"))
      (node (ref "U1") (pin "55") (pinfunction "QSPI_SD1_55") (pintype "bidirectional"))
    )
    (net (code "45") (name "Net-(IC1-IO2)") (class "Default")
      (node (ref "IC1") (pin "3") (pinfunction "IO2_3") (pintype "passive"))
      (node (ref "U1") (pin "54") (pinfunction "QSPI_SD2_54") (pintype "bidirectional"))
    )
    (net (code "46") (name "Net-(IC1-IO3)") (class "Default")
      (node (ref "IC1") (pin "7") (pinfunction "IO3_7") (pintype "passive"))
      (node (ref "U1") (pin "51") (pinfunction "QSPI_SD3_51") (pintype "bidirectional"))
    )
    (net (code "47") (name "Net-(LED1-A)") (class "Default")
      (node (ref "LED1") (pin "2") (pinfunction "A_2") (pintype "passive"))
      (node (ref "R10") (pin "1") (pinfunction "1_1") (pintype "passive"))
    )
    (net (code "48") (name "Net-(LED4-A)") (class "Default")
      (node (ref "LED4") (pin "2") (pinfunction "A_2") (pintype "passive"))
      (node (ref "R23") (pin "1") (pinfunction "1_1") (pintype "passive"))
    )
    (net (code "49") (name "Net-(R11-Pad2)") (class "Default")
      (node (ref "R11") (pin "2") (pinfunction "2_2") (pintype "passive"))
      (node (ref "R8") (pin "2") (pinfunction "2_2") (pintype "passive"))
    )
    (net (code "50") (name "Net-(R47-Pad1)") (class "Default")
      (node (ref "R47") (pin "1") (pinfunction "1_1") (pintype "passive"))
      (node (ref "R48") (pin "1") (pinfunction "1_1") (pintype "passive"))
      (node (ref "SW3") (pin "1") (pinfunction "1_1") (pintype "passive"))
    )
    (net (code "51") (name "Net-(R49-Pad1)") (class "Default")
      (node (ref "R49") (pin "1") (pinfunction "1_1") (pintype "passive"))
      (node (ref "R50") (pin "1") (pinfunction "1_1") (pintype "passive"))
      (node (ref "SW6") (pin "1") (pinfunction "1_1") (pintype "passive"))
    )
    (net (code "52") (name "Net-(R51-Pad1)") (class "Default")
      (node (ref "R51") (pin "1") (pinfunction "1_1") (pintype "passive"))
      (node (ref "R52") (pin "1") (pinfunction "1_1") (pintype "passive"))
      (node (ref "SW4") (pin "1") (pinfunction "1_1") (pintype "passive"))
    )
    (net (code "53") (name "Net-(SW4-A)") (class "Default")
      (node (ref "R19") (pin "1") (pinfunction "1_1") (pintype "passive"))
      (node (ref "R20") (pin "2") (pinfunction "2_2") (pintype "passive"))
      (node (ref "SW4") (pin "5") (pinfunction "A_5") (pintype "passive"))
    )
    (net (code "54") (name "Net-(SW4-B)") (class "Default")
      (node (ref "R21") (pin "1") (pinfunction "1_1") (pintype "passive"))
      (node (ref "R22") (pin "2") (pinfunction "2_2") (pintype "passive"))
      (node (ref "SW4") (pin "3") (pinfunction "B_3") (pintype "passive"))
    )
    (net (code "55") (name "Net-(SW6-A)") (class "Default")
      (node (ref "R17") (pin "1") (pinfunction "1_1") (pintype "passive"))
      (node (ref "R18") (pin "2") (pinfunction "2_2") (pintype "passive"))
      (node (ref "SW6") (pin "5") (pinfunction "A_5") (pintype "passive"))
    )
    (net (code "56") (name "Net-(SW6-B)") (class "Default")
      (node (ref "R58") (pin "1") (pinfunction "1_1") (pintype "passive"))
      (node (ref "R59") (pin "2") (pinfunction "2_2") (pintype "passive"))
      (node (ref "SW6") (pin "3") (pinfunction "B_3") (pintype "passive"))
    )
    (net (code "57") (name "Net-(U1A-GPIO21)") (class "Default")
      (node (ref "TP1") (pin "1") (pinfunction "1_1") (pintype "passive"))
      (node (ref "U1") (pin "32") (pinfunction "GPIO21_32") (pintype "bidirectional"))
    )
    (net (code "58") (name "Net-(U1A-GPIO22)") (class "Default")
      (node (ref "TP2") (pin "1") (pinfunction "1_1") (pintype "passive"))
      (node (ref "U1") (pin "34") (pinfunction "GPIO22_34") (pintype "bidirectional"))
    )
    (net (code "59") (name "Net-(U1A-GPIO23)") (class "Default")
      (node (ref "TP3") (pin "1") (pinfunction "1_1") (pintype "passive"))
      (node (ref "U1") (pin "35") (pinfunction "GPIO23_35") (pintype "bidirectional"))
    )
    (net (code "60") (name "Net-(U1A-GPIO25)") (class "Default")
      (node (ref "R10") (pin "2") (pinfunction "2_2") (pintype "passive"))
      (node (ref "U1") (pin "37") (pinfunction "GPIO25_37") (pintype "bidirectional"))
    )
    (net (code "61") (name "Net-(U1A-XIN)") (class "Default")
      (node (ref "C1") (pin "2") (pinfunction "2_2") (pintype "passive"))
      (node (ref "U1") (pin "20") (pinfunction "XIN_20") (pintype "passive"))
      (node (ref "X1") (pin "1") (pinfunction "1_Xtal_1") (pintype "passive"))
    )
    (net (code "62") (name "Net-(U1A-XOUT)") (class "Default")
      (node (ref "R9") (pin "1") (pinfunction "1_1") (pintype "passive"))
      (node (ref "U1") (pin "21") (pinfunction "XOUT_21") (pintype "output"))
    )
    (net (code "63") (name "Net-(X1-2_Xtal)") (class "Default")
      (node (ref "C2") (pin "2") (pinfunction "2_2") (pintype "passive"))
      (node (ref "R9") (pin "2") (pinfunction "2_2") (pintype "passive"))
      (node (ref "X1") (pin "3") (pinfunction "2_Xtal_3") (pintype "passive"))
    )
    (net (code "64") (name "unconnected-(CN1-0=MCU_1=SPI-Pad3)") (class "Default")
      (node (ref "CN1") (pin "3") (pinfunction "0=MCU_1=SPI_3") (pintype "passive"))
    )
    (net (code "65") (name "unconnected-(CN1-CS-Pad9)") (class "Default")
      (node (ref "CN1") (pin "9") (pinfunction "CS_9") (pintype "passive"))
    )
    (net (code "66") (name "unconnected-(CN1-CTP_INT-Pad5)") (class "Default")
      (node (ref "CN1") (pin "5") (pinfunction "CTP_INT_5") (pintype "passive"))
    )
    (net (code "67") (name "unconnected-(CN1-CTP_RST-Pad31)") (class "Default")
      (node (ref "CN1") (pin "31") (pinfunction "CTP_RST_31") (pintype "passive"))
    )
    (net (code "68") (name "unconnected-(CN1-CTP_SCL-Pad6)") (class "Default")
      (node (ref "CN1") (pin "6") (pinfunction "CTP_SCL_6") (pintype "passive"))
    )
    (net (code "69") (name "unconnected-(CN1-CTP_SDA-Pad32)") (class "Default")
      (node (ref "CN1") (pin "32") (pinfunction "CTP_SDA_32") (pintype "passive"))
    )
    (net (code "70") (name "unconnected-(CN1-DB0(GND)-Pad25)") (class "Default")
      (node (ref "CN1") (pin "25") (pinfunction "DB0(GND)_25") (pintype "passive"))
    )
    (net (code "71") (name "unconnected-(CN1-DB1(GND)-Pad26)") (class "Default")
      (node (ref "CN1") (pin "26") (pinfunction "DB1(GND)_26") (pintype "passive"))
    )
    (net (code "72") (name "unconnected-(CN1-DB2(GND)-Pad27)") (class "Default")
      (node (ref "CN1") (pin "27") (pinfunction "DB2(GND)_27") (pintype "passive"))
    )
    (net (code "73") (name "unconnected-(CN1-DB3(GND)-Pad28)") (class "Default")
      (node (ref "CN1") (pin "28") (pinfunction "DB3(GND)_28") (pintype "passive"))
    )
    (net (code "74") (name "unconnected-(CN1-DB4(GND)-Pad29)") (class "Default")
      (node (ref "CN1") (pin "29") (pinfunction "DB4(GND)_29") (pintype "passive"))
    )
    (net (code "75") (name "unconnected-(CN1-DB5(GND)-Pad30)") (class "Default")
      (node (ref "CN1") (pin "30") (pinfunction "DB5(GND)_30") (pintype "passive"))
    )
    (net (code "76") (name "unconnected-(CN1-DB6(GND)-Pad24)") (class "Default")
      (node (ref "CN1") (pin "24") (pinfunction "DB6(GND)_24") (pintype "passive"))
    )
    (net (code "77") (name "unconnected-(CN1-DB7(GND)-Pad23)") (class "Default")
      (node (ref "CN1") (pin "23") (pinfunction "DB7(GND)_23") (pintype "passive"))
    )
    (net (code "78") (name "unconnected-(CN1-DB8(GND)-Pad22)") (class "Default")
      (node (ref "CN1") (pin "22") (pinfunction "DB8(GND)_22") (pintype "passive"))
    )
    (net (code "79") (name "unconnected-(CN1-DB9(GND)-Pad21)") (class "Default")
      (node (ref "CN1") (pin "21") (pinfunction "DB9(GND)_21") (pintype "passive"))
    )
    (net (code "80") (name "unconnected-(CN1-DB10(GND)-Pad20)") (class "Default")
      (node (ref "CN1") (pin "20") (pinfunction "DB10(GND)_20") (pintype "passive"))
    )
    (net (code "81") (name "unconnected-(CN1-DB11(GND)-Pad19)") (class "Default")
      (node (ref "CN1") (pin "19") (pinfunction "DB11(GND)_19") (pintype "passive"))
    )
    (net (code "82") (name "unconnected-(CN1-DB12(GND)-Pad18)") (class "Default")
      (node (ref "CN1") (pin "18") (pinfunction "DB12(GND)_18") (pintype "passive"))
    )
    (net (code "83") (name "unconnected-(CN1-DB13(GND)-Pad17)") (class "Default")
      (node (ref "CN1") (pin "17") (pinfunction "DB13(GND)_17") (pintype "passive"))
    )
    (net (code "84") (name "unconnected-(CN1-DB14(GND)-Pad16)") (class "Default")
      (node (ref "CN1") (pin "16") (pinfunction "DB14(GND)_16") (pintype "passive"))
    )
    (net (code "85") (name "unconnected-(CN1-DB15(GND)-Pad15)") (class "Default")
      (node (ref "CN1") (pin "15") (pinfunction "DB15(GND)_15") (pintype "passive"))
    )
    (net (code "86") (name "unconnected-(CN1-FMARK-Pad4)") (class "Default")
      (node (ref "CN1") (pin "4") (pinfunction "FMARK_4") (pintype "passive"))
    )
    (net (code "87") (name "unconnected-(CN1-GND(SDI)-Pad2)") (class "Default")
      (node (ref "CN1") (pin "2") (pinfunction "GND(SDI)_2") (pintype "passive"))
    )
    (net (code "88") (name "unconnected-(CN1-GND-Pad1)") (class "Default")
      (node (ref "CN1") (pin "1") (pinfunction "GND_1") (pintype "passive"))
    )
    (net (code "89") (name "unconnected-(CN1-GND-Pad14)") (class "Default")
      (node (ref "CN1") (pin "14") (pinfunction "GND_14") (pintype "passive"))
    )
    (net (code "90") (name "unconnected-(CN1-GND-Pad40)") (class "Default")
      (node (ref "CN1") (pin "40") (pinfunction "GND_40") (pintype "passive"))
    )
    (net (code "91") (name "unconnected-(CN1-LEDA-Pad33)") (class "Default")
      (node (ref "CN1") (pin "33") (pinfunction "LEDA_33") (pintype "passive"))
    )
    (net (code "92") (name "unconnected-(CN1-LEDK1-Pad34)") (class "Default")
      (node (ref "CN1") (pin "34") (pinfunction "LEDK1_34") (pintype "passive"))
    )
    (net (code "93") (name "unconnected-(CN1-LEDK2-Pad35)") (class "Default")
      (node (ref "CN1") (pin "35") (pinfunction "LEDK2_35") (pintype "passive"))
    )
    (net (code "94") (name "unconnected-(CN1-LEDK3-Pad36)") (class "Default")
      (node (ref "CN1") (pin "36") (pinfunction "LEDK3_36") (pintype "passive"))
    )
    (net (code "95") (name "unconnected-(CN1-LEDK4-Pad37)") (class "Default")
      (node (ref "CN1") (pin "37") (pinfunction "LEDK4_37") (pintype "passive"))
    )
    (net (code "96") (name "unconnected-(CN1-LEDK5-Pad38)") (class "Default")
      (node (ref "CN1") (pin "38") (pinfunction "LEDK5_38") (pintype "passive"))
    )
    (net (code "97") (name "unconnected-(CN1-LEDK6-Pad39)") (class "Default")
      (node (ref "CN1") (pin "39") (pinfunction "LEDK6_39") (pintype "passive"))
    )
    (net (code "98") (name "unconnected-(CN1-NC{slash}(SDO)-Pad13)") (class "Default")
      (node (ref "CN1") (pin "13") (pinfunction "NC/(SDO)_13") (pintype "passive"))
    )
    (net (code "99") (name "unconnected-(CN1-RD{slash}(VCC)-Pad10)") (class "Default")
      (node (ref "CN1") (pin "10") (pinfunction "RD/(VCC)_10") (pintype "passive"))
    )
    (net (code "100") (name "unconnected-(CN1-RESET-Pad7)") (class "Default")
      (node (ref "CN1") (pin "7") (pinfunction "RESET_7") (pintype "passive"))
    )
    (net (code "101") (name "unconnected-(CN1-RS{slash}(SCK)-Pad8)") (class "Default")
      (node (ref "CN1") (pin "8") (pinfunction "RS/(SCK)_8") (pintype "passive"))
    )
    (net (code "102") (name "unconnected-(CN1-RW{slash}(D{slash}C)-Pad11)") (class "Default")
      (node (ref "CN1") (pin "11") (pinfunction "RW/(D/C)_11") (pintype "passive"))
    )
    (net (code "103") (name "unconnected-(CN1-VCC-Pad12)") (class "Default")
      (node (ref "CN1") (pin "12") (pinfunction "VCC_12") (pintype "passive"))
    )
    (net (code "104") (name "unconnected-(CN2-NC-Pad41)") (class "Default")
      (node (ref "CN2") (pin "41") (pinfunction "NC_41") (pintype "passive"))
    )
    (net (code "105") (name "unconnected-(CN2-NC-Pad42)") (class "Default")
      (node (ref "CN2") (pin "42") (pinfunction "NC_42") (pintype "passive"))
    )
    (net (code "106") (name "unconnected-(CN2-Pad4)") (class "Default")
      (node (ref "CN2") (pin "4") (pintype "bidirectional+no_connect"))
    )
    (net (code "107") (name "unconnected-(CN2-Pad5)") (class "Default")
      (node (ref "CN2") (pin "5") (pintype "bidirectional+no_connect"))
    )
    (net (code "108") (name "unconnected-(CN2-Pad6)") (class "Default")
      (node (ref "CN2") (pin "6") (pintype "bidirectional+no_connect"))
    )
    (net (code "109") (name "unconnected-(CN2-Pad31)") (class "Default")
      (node (ref "CN2") (pin "31") (pintype "bidirectional+no_connect"))
    )
    (net (code "110") (name "unconnected-(CN2-Pad32)") (class "Default")
      (node (ref "CN2") (pin "32") (pintype "bidirectional+no_connect"))
    )
    (net (code "111") (name "unconnected-(J5-Pad2)") (class "Default")
      (node (ref "J5") (pin "2") (pinfunction "2_2") (pintype "passive"))
    )
    (net (code "112") (name "unconnected-(J5-Pad7)") (class "Default")
      (node (ref "J5") (pin "7") (pinfunction "7_7") (pintype "passive"))
    )
    (net (code "113") (name "unconnected-(J5-Pad8)") (class "Default")
      (node (ref "J5") (pin "8") (pinfunction "8_8") (pintype "passive"))
    )
    (net (code "114") (name "unconnected-(J5-Pad9)") (class "Default")
      (node (ref "J5") (pin "9") (pinfunction "9_9") (pintype "passive"))
    )
    (net (code "115") (name "unconnected-(J5-Pad10)") (class "Default")
      (node (ref "J5") (pin "10") (pinfunction "10_10") (pintype "passive"))
    )
    (net (code "116") (name "unconnected-(SW3-Pad2)") (class "Default")
      (node (ref "SW3") (pin "2") (pinfunction "2_2") (pintype "passive"))
    )
    (net (code "117") (name "unconnected-(SW3-Pad3)") (class "Default")
      (node (ref "SW3") (pin "3") (pinfunction "3_3") (pintype "passive"))
    )
  )
)
